# VSCard_v2.net
KiCad netlist of a schematic drawn in EAGLE
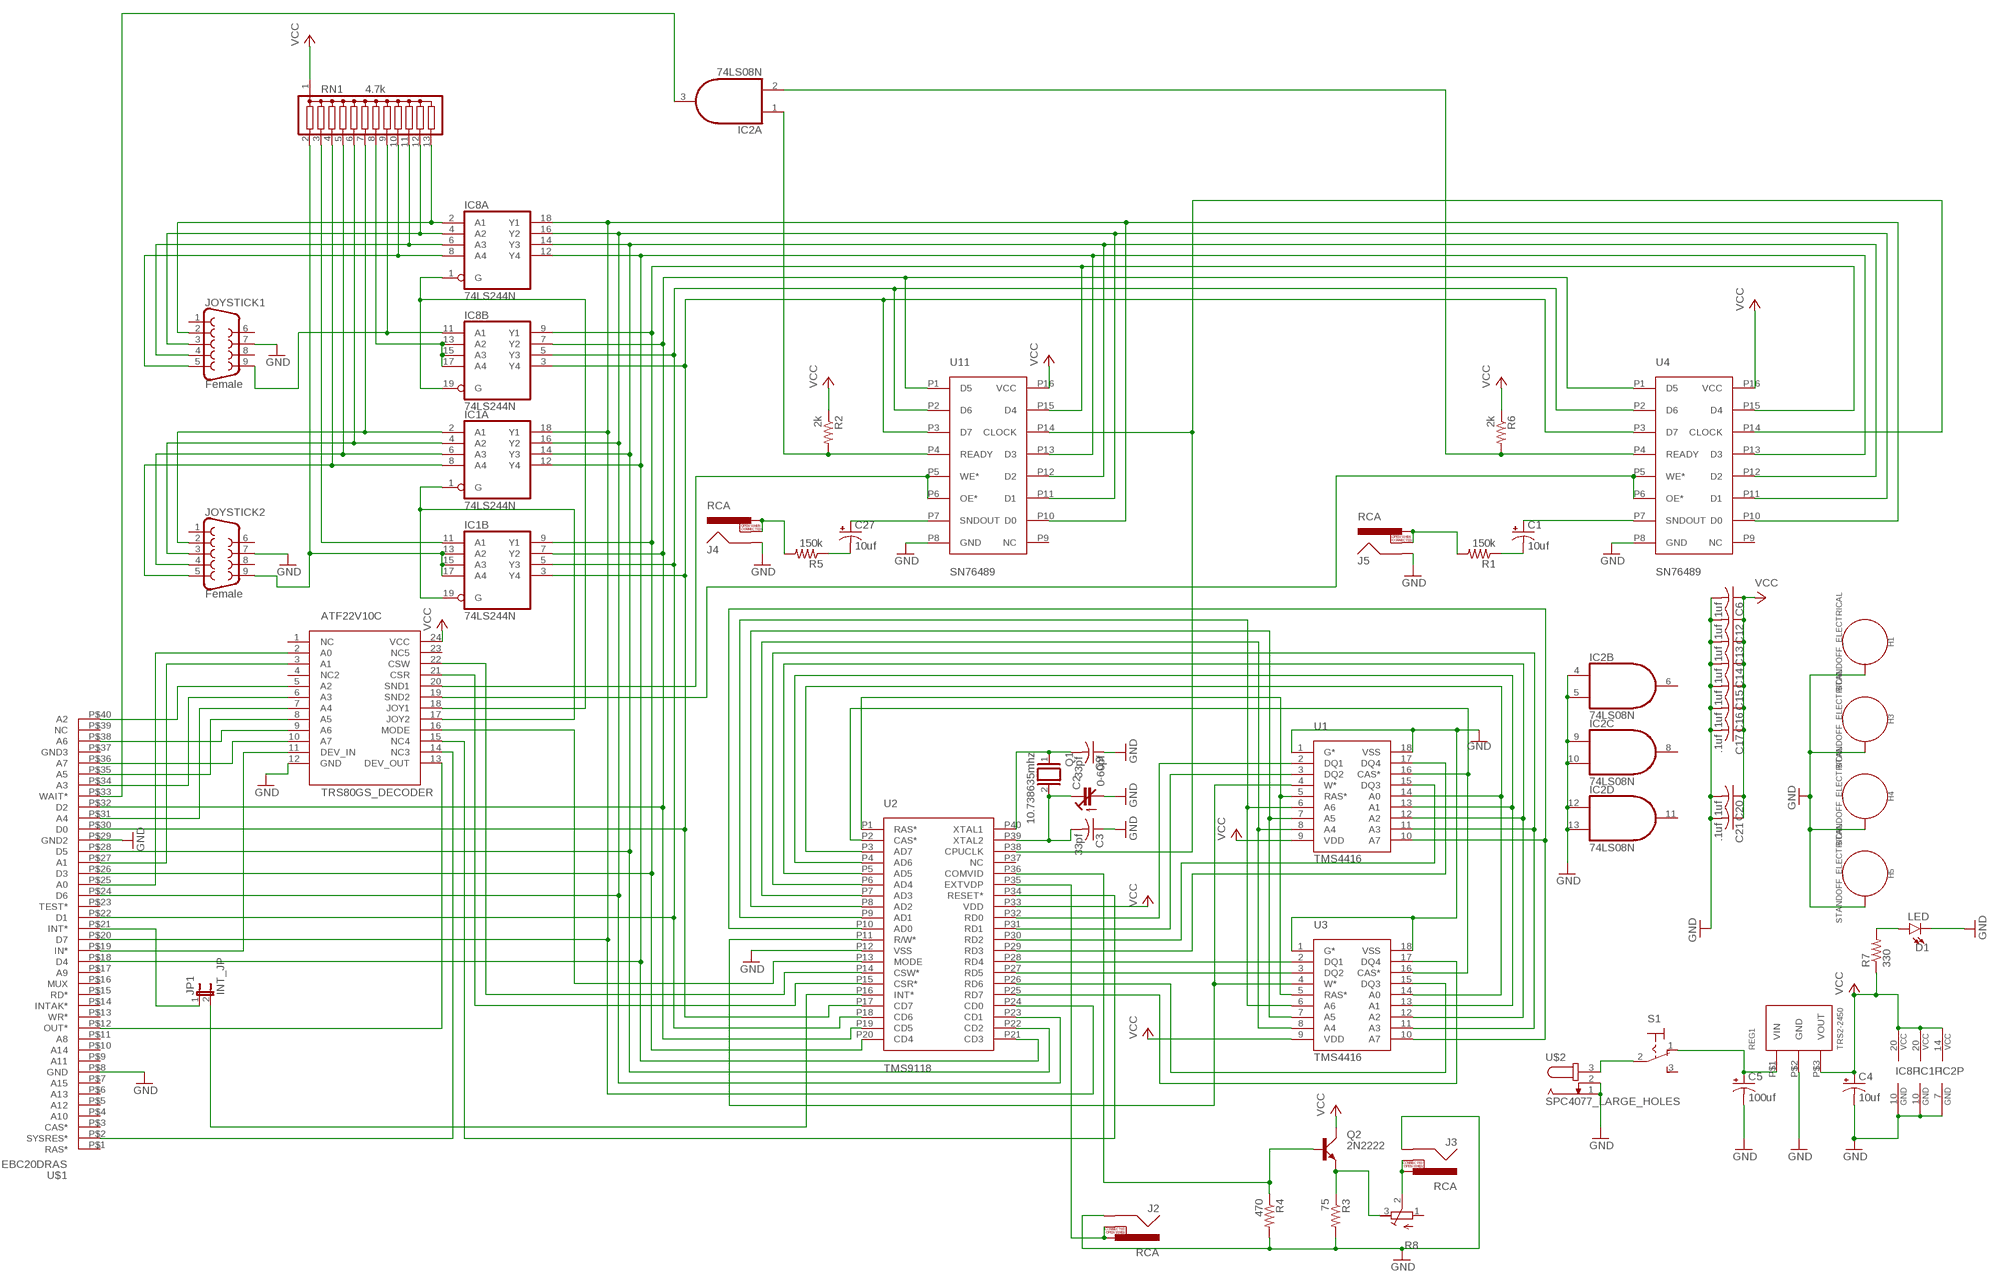
[diagram p0: schematic, sheet 1]

(export (version "E")
  (design (tool "Eeschema 10.0.6"))
  (components
    (comp (ref "ATF22V10C")
      (value "TRS80GS_DECODER")
      (footprint "eagle-import:DIP24SKI")
      (libsource (lib "eagle-import") (part "TRS80GS_DECODER"))
    )
    (comp (ref "C1")
      (value "10uf")
      (footprint "eagle-import:E2,5-6")
      (libsource (lib "eagle-import") (part "resistor_348_CPOL-USE2.5-6"))
    )
    (comp (ref "C2")
      (value "0-60pf")
      (footprint "eagle-import:CTRIM3050.504")
      (libsource (lib "eagle-import") (part "C-TRIMM3050.504"))
    )
    (comp (ref "C3")
      (value "33pf")
      (footprint "eagle-import:C050-050X075")
      (libsource (lib "eagle-import") (part "C-US050-050X075"))
    )
    (comp (ref "C4")
      (value "10uf")
      (footprint "eagle-import:E2,5-5")
      (libsource (lib "eagle-import") (part "resistor_348_CPOL-USE2.5-5"))
    )
    (comp (ref "C5")
      (value "100uf")
      (footprint "eagle-import:E3,5-10")
      (libsource (lib "eagle-import") (part "CPOL-USE3.5-10"))
    )
    (comp (ref "C6")
      (value ".1uf")
      (footprint "eagle-import:C025-025X050")
      (libsource (lib "eagle-import") (part "resistor_348_C-US025-025X050"))
    )
    (comp (ref "C9")
      (value "33pf")
      (footprint "eagle-import:C050-050X075")
      (libsource (lib "eagle-import") (part "C-US050-050X075"))
    )
    (comp (ref "C12")
      (value ".1uf")
      (footprint "eagle-import:C025-025X050")
      (libsource (lib "eagle-import") (part "resistor_348_C-US025-025X050"))
    )
    (comp (ref "C13")
      (value ".1uf")
      (footprint "eagle-import:C025-025X050")
      (libsource (lib "eagle-import") (part "resistor_348_C-US025-025X050"))
    )
    (comp (ref "C14")
      (value ".1uf")
      (footprint "eagle-import:C025-025X050")
      (libsource (lib "eagle-import") (part "resistor_348_C-US025-025X050"))
    )
    (comp (ref "C15")
      (value ".1uf")
      (footprint "eagle-import:C025-025X050")
      (libsource (lib "eagle-import") (part "resistor_348_C-US025-025X050"))
    )
    (comp (ref "C16")
      (value ".1uf")
      (footprint "eagle-import:C025-025X050")
      (libsource (lib "eagle-import") (part "resistor_348_C-US025-025X050"))
    )
    (comp (ref "C17")
      (value ".1uf")
      (footprint "eagle-import:C025-025X050")
      (libsource (lib "eagle-import") (part "resistor_348_C-US025-025X050"))
    )
    (comp (ref "C20")
      (value ".1uf")
      (footprint "eagle-import:C025-025X050")
      (libsource (lib "eagle-import") (part "resistor_348_C-US025-025X050"))
    )
    (comp (ref "C21")
      (value ".1uf")
      (footprint "eagle-import:C025-025X050")
      (libsource (lib "eagle-import") (part "resistor_348_C-US025-025X050"))
    )
    (comp (ref "C27")
      (value "10uf")
      (footprint "eagle-import:E2,5-6")
      (libsource (lib "eagle-import") (part "resistor_348_CPOL-USE2.5-6"))
    )
    (comp (ref "D1")
      (value "LED")
      (footprint "eagle-import:LED_3MM")
      (libsource (lib "eagle-import") (part "LED3MM"))
    )
    (comp (ref "H1")
      (value "STANDOFF_ELECTRICAL")
      (footprint "eagle-import:STANDOFF-ELECTRICAL")
      (libsource (lib "eagle-import") (part "STANDOFF_ELECTRICAL"))
    )
    (comp (ref "H3")
      (value "STANDOFF_ELECTRICAL")
      (footprint "eagle-import:STANDOFF-ELECTRICAL")
      (libsource (lib "eagle-import") (part "STANDOFF_ELECTRICAL"))
    )
    (comp (ref "H4")
      (value "STANDOFF_ELECTRICAL")
      (footprint "eagle-import:STANDOFF-ELECTRICAL")
      (libsource (lib "eagle-import") (part "STANDOFF_ELECTRICAL"))
    )
    (comp (ref "H5")
      (value "STANDOFF_ELECTRICAL")
      (footprint "eagle-import:STANDOFF-ELECTRICAL")
      (libsource (lib "eagle-import") (part "STANDOFF_ELECTRICAL"))
    )
    (comp (ref "IC1")
      (value "74LS244N")
      (footprint "eagle-import:DIL20")
      (libsource (lib "eagle-import") (part "74244NLS"))
    )
    (comp (ref "IC2")
      (value "74LS08N")
      (footprint "eagle-import:DIL14")
      (libsource (lib "eagle-import") (part "7408NLS"))
    )
    (comp (ref "IC8")
      (value "74LS244N")
      (footprint "eagle-import:DIL20")
      (libsource (lib "eagle-import") (part "74244NLS"))
    )
    (comp (ref "J2")
      (value "RCA")
      (footprint "eagle-import:RCA")
      (libsource (lib "eagle-import") (part "RCA"))
    )
    (comp (ref "J3")
      (value "RCA")
      (footprint "eagle-import:RCA")
      (libsource (lib "eagle-import") (part "RCA"))
    )
    (comp (ref "J4")
      (value "RCA")
      (footprint "eagle-import:RCA")
      (libsource (lib "eagle-import") (part "RCA"))
    )
    (comp (ref "J5")
      (value "RCA")
      (footprint "eagle-import:RCA")
      (libsource (lib "eagle-import") (part "RCA"))
    )
    (comp (ref "JOYSTICK1")
      (value "Female")
      (footprint "eagle-import:DB9")
      (libsource (lib "eagle-import") (part "DB9FEMALE"))
    )
    (comp (ref "JOYSTICK2")
      (value "Female")
      (footprint "eagle-import:DB9")
      (libsource (lib "eagle-import") (part "DB9FEMALE"))
    )
    (comp (ref "JP1")
      (value "INT_JP")
      (footprint "eagle-import:JP1")
      (libsource (lib "eagle-import") (part "JP1E"))
    )
    (comp (ref "Q1")
      (value "10.738635mhz")
      (footprint "eagle-import:QS")
      (libsource (lib "eagle-import") (part "XTAL/S"))
    )
    (comp (ref "Q2")
      (value "2N2222")
      (footprint "eagle-import:TO18A")
      (libsource (lib "eagle-import") (part "2N2222"))
    )
    (comp (ref "R1")
      (value "150k")
      (footprint "eagle-import:0207_2V")
      (libsource (lib "eagle-import") (part "R-US_0207/2V"))
    )
    (comp (ref "R2")
      (value "2k")
      (footprint "eagle-import:0207_2V")
      (libsource (lib "eagle-import") (part "R-US_0207/2V"))
    )
    (comp (ref "R3")
      (value "75")
      (footprint "eagle-import:0207_2V")
      (libsource (lib "eagle-import") (part "R-US_0207/2V"))
    )
    (comp (ref "R4")
      (value "470")
      (footprint "eagle-import:0207_2V")
      (libsource (lib "eagle-import") (part "R-US_0207/2V"))
    )
    (comp (ref "R5")
      (value "150k")
      (footprint "eagle-import:0207_2V")
      (libsource (lib "eagle-import") (part "R-US_0207/2V"))
    )
    (comp (ref "R6")
      (value "2k")
      (footprint "eagle-import:0207_2V")
      (libsource (lib "eagle-import") (part "R-US_0207/2V"))
    )
    (comp (ref "R7")
      (value "330")
      (footprint "eagle-import:0309V")
      (libsource (lib "eagle-import") (part "R-US_0309/V"))
    )
    (comp (ref "R8")
      (value "R-TRIMM64W")
      (footprint "eagle-import:RTRIM64W")
      (libsource (lib "eagle-import") (part "R-TRIMM64W"))
    )
    (comp (ref "REG1")
      (value "TRS2-2450")
      (footprint "eagle-import:TRACON_REG")
      (libsource (lib "eagle-import") (part "TRS2-2450"))
    )
    (comp (ref "RN1")
      (value "4.7k")
      (footprint "eagle-import:SIL13")
      (libsource (lib "eagle-import") (part "G12R"))
    )
    (comp (ref "S1")
      (value "320-916")
      (footprint "eagle-import:320-916")
      (libsource (lib "eagle-import") (part "320-916"))
    )
    (comp (ref "U$1")
      (value "EBC20DRAS")
      (footprint "eagle-import:EBC20DRAS")
      (libsource (lib "eagle-import") (part "EBC20DRAS"))
    )
    (comp (ref "U$2")
      (value "SPC4077_LARGE_HOLES")
      (footprint "eagle-import:SPC4077")
      (libsource (lib "eagle-import") (part "SPC4077_LARGE_HOLES"))
    )
    (comp (ref "U1")
      (value "TMS4416")
      (footprint "eagle-import:DIP18")
      (libsource (lib "eagle-import") (part "TMS4416"))
    )
    (comp (ref "U2")
      (value "TMS9118")
      (footprint "eagle-import:DIP40_MCU")
      (libsource (lib "eagle-import") (part "TMS9118"))
    )
    (comp (ref "U3")
      (value "TMS4416")
      (footprint "eagle-import:DIP18")
      (libsource (lib "eagle-import") (part "TMS4416"))
    )
    (comp (ref "U4")
      (value "SN76489")
      (footprint "eagle-import:DIP16")
      (libsource (lib "eagle-import") (part "SN76489"))
    )
    (comp (ref "U11")
      (value "SN76489")
      (footprint "eagle-import:DIP16")
      (libsource (lib "eagle-import") (part "SN76489"))
    )
  )
  (nets
    (net (code "1") (name "GND") (class "Default")
      (node (ref "ATF22V10C") (pin "12") (pinfunction "GND_12") (pintype "bidirectional"))
      (node (ref "C12") (pin "2") (pinfunction "2_2") (pintype "passive"))
      (node (ref "C13") (pin "2") (pinfunction "2_2") (pintype "passive"))
      (node (ref "C14") (pin "2") (pinfunction "2_2") (pintype "passive"))
      (node (ref "C15") (pin "2") (pinfunction "2_2") (pintype "passive"))
      (node (ref "C16") (pin "2") (pinfunction "2_2") (pintype "passive"))
      (node (ref "C17") (pin "2") (pinfunction "2_2") (pintype "passive"))
      (node (ref "C2") (pin "2") (pinfunction "A_2") (pintype "passive"))
      (node (ref "C20") (pin "2") (pinfunction "2_2") (pintype "passive"))
      (node (ref "C21") (pin "2") (pinfunction "2_2") (pintype "passive"))
      (node (ref "C3") (pin "1") (pinfunction "1_1") (pintype "passive"))
      (node (ref "C4") (pin "-") (pinfunction "-_-") (pintype "passive"))
      (node (ref "C5") (pin "-") (pinfunction "-_-") (pintype "passive"))
      (node (ref "C6") (pin "2") (pinfunction "2_2") (pintype "passive"))
      (node (ref "C9") (pin "1") (pinfunction "1_1") (pintype "passive"))
      (node (ref "D1") (pin "K") (pinfunction "C_K") (pintype "passive"))
      (node (ref "H1") (pin "P1") (pinfunction "P$1_P1") (pintype "bidirectional"))
      (node (ref "H3") (pin "P1") (pinfunction "P$1_P1") (pintype "bidirectional"))
      (node (ref "H4") (pin "P1") (pinfunction "P$1_P1") (pintype "bidirectional"))
      (node (ref "H5") (pin "P1") (pinfunction "P$1_P1") (pintype "bidirectional"))
      (node (ref "IC1") (pin "10") (pinfunction "GND_10") (pintype "power_in"))
      (node (ref "IC2") (pin "10") (pinfunction "I1_10") (pintype "input"))
      (node (ref "IC2") (pin "12") (pinfunction "I0_12") (pintype "input"))
      (node (ref "IC2") (pin "13") (pinfunction "I1_13") (pintype "input"))
      (node (ref "IC2") (pin "4") (pinfunction "I0_4") (pintype "input"))
      (node (ref "IC2") (pin "5") (pinfunction "I1_5") (pintype "input"))
      (node (ref "IC2") (pin "7") (pinfunction "GND_7") (pintype "power_in"))
      (node (ref "IC2") (pin "9") (pinfunction "I0_9") (pintype "input"))
      (node (ref "IC8") (pin "10") (pinfunction "GND_10") (pintype "power_in"))
      (node (ref "J2") (pin "SHELL") (pinfunction "SHELL_SHELL") (pintype "bidirectional"))
      (node (ref "J3") (pin "SHELL") (pinfunction "SHELL_SHELL") (pintype "bidirectional"))
      (node (ref "J4") (pin "SHELL") (pinfunction "SHELL_SHELL") (pintype "bidirectional"))
      (node (ref "J5") (pin "SHELL") (pinfunction "SHELL_SHELL") (pintype "bidirectional"))
      (node (ref "JOYSTICK1") (pin "7") (pinfunction "7_7") (pintype "passive"))
      (node (ref "JOYSTICK2") (pin "7") (pinfunction "7_7") (pintype "passive"))
      (node (ref "R3") (pin "2") (pinfunction "2_2") (pintype "passive"))
      (node (ref "R4") (pin "2") (pinfunction "2_2") (pintype "passive"))
      (node (ref "REG1") (pin "P$2") (pinfunction "GND_P$2") (pintype "bidirectional"))
      (node (ref "U$1") (pin "P$29") (pinfunction "GND2_P$29") (pintype "bidirectional"))
      (node (ref "U$1") (pin "P$8") (pinfunction "GND_P$8") (pintype "bidirectional"))
      (node (ref "U$2") (pin "1") (pinfunction "1_1") (pintype "passive"))
      (node (ref "U$2") (pin "2") (pinfunction "2_2") (pintype "passive"))
      (node (ref "U1") (pin "1") (pinfunction "G*_1") (pintype "bidirectional"))
      (node (ref "U1") (pin "18") (pinfunction "VSS_18") (pintype "bidirectional"))
      (node (ref "U11") (pin "P8") (pinfunction "GND_P8") (pintype "bidirectional"))
      (node (ref "U2") (pin "P12") (pinfunction "VSS_P12") (pintype "bidirectional"))
      (node (ref "U3") (pin "1") (pinfunction "G*_1") (pintype "bidirectional"))
      (node (ref "U3") (pin "18") (pinfunction "VSS_18") (pintype "bidirectional"))
      (node (ref "U4") (pin "P8") (pinfunction "GND_P8") (pintype "bidirectional"))
    )
    (net (code "2") (name "Net-(ATF22V10C-A0)") (class "Default")
      (node (ref "ATF22V10C") (pin "2") (pinfunction "A0_2") (pintype "bidirectional"))
      (node (ref "U$1") (pin "P$25") (pinfunction "A0_P$25") (pintype "bidirectional"))
    )
    (net (code "3") (name "Net-(ATF22V10C-A1)") (class "Default")
      (node (ref "ATF22V10C") (pin "3") (pinfunction "A1_3") (pintype "bidirectional"))
      (node (ref "U$1") (pin "P$27") (pinfunction "A1_P$27") (pintype "bidirectional"))
    )
    (net (code "4") (name "Net-(ATF22V10C-A2)") (class "Default")
      (node (ref "ATF22V10C") (pin "5") (pinfunction "A2_5") (pintype "bidirectional"))
      (node (ref "U$1") (pin "P$40") (pinfunction "A2_P$40") (pintype "bidirectional"))
    )
    (net (code "5") (name "Net-(ATF22V10C-A3)") (class "Default")
      (node (ref "ATF22V10C") (pin "6") (pinfunction "A3_6") (pintype "bidirectional"))
      (node (ref "U$1") (pin "P$34") (pinfunction "A3_P$34") (pintype "bidirectional"))
    )
    (net (code "6") (name "Net-(ATF22V10C-A4)") (class "Default")
      (node (ref "ATF22V10C") (pin "7") (pinfunction "A4_7") (pintype "bidirectional"))
      (node (ref "U$1") (pin "P$31") (pinfunction "A4_P$31") (pintype "bidirectional"))
    )
    (net (code "7") (name "Net-(ATF22V10C-A5)") (class "Default")
      (node (ref "ATF22V10C") (pin "8") (pinfunction "A5_8") (pintype "bidirectional"))
      (node (ref "U$1") (pin "P$35") (pinfunction "A5_P$35") (pintype "bidirectional"))
    )
    (net (code "8") (name "Net-(ATF22V10C-A6)") (class "Default")
      (node (ref "ATF22V10C") (pin "9") (pinfunction "A6_9") (pintype "bidirectional"))
      (node (ref "U$1") (pin "P$38") (pinfunction "A6_P$38") (pintype "bidirectional"))
    )
    (net (code "9") (name "Net-(ATF22V10C-A7)") (class "Default")
      (node (ref "ATF22V10C") (pin "10") (pinfunction "A7_10") (pintype "bidirectional"))
      (node (ref "U$1") (pin "P$36") (pinfunction "A7_P$36") (pintype "bidirectional"))
    )
    (net (code "10") (name "Net-(ATF22V10C-CSR)") (class "Default")
      (node (ref "ATF22V10C") (pin "21") (pinfunction "CSR_21") (pintype "bidirectional"))
      (node (ref "U2") (pin "P15") (pinfunction "CSR*_P15") (pintype "bidirectional"))
    )
    (net (code "11") (name "Net-(ATF22V10C-CSW)") (class "Default")
      (node (ref "ATF22V10C") (pin "22") (pinfunction "CSW_22") (pintype "bidirectional"))
      (node (ref "U2") (pin "P14") (pinfunction "CSW*_P14") (pintype "bidirectional"))
    )
    (net (code "12") (name "Net-(ATF22V10C-DEV_IN)") (class "Default")
      (node (ref "ATF22V10C") (pin "11") (pinfunction "DEV_IN_11") (pintype "bidirectional"))
      (node (ref "U$1") (pin "P$19") (pinfunction "IN*_P$19") (pintype "bidirectional"))
    )
    (net (code "13") (name "Net-(ATF22V10C-DEV_OUT)") (class "Default")
      (node (ref "ATF22V10C") (pin "13") (pinfunction "DEV_OUT_13") (pintype "bidirectional"))
      (node (ref "U$1") (pin "P$12") (pinfunction "OUT*_P$12") (pintype "bidirectional"))
    )
    (net (code "14") (name "Net-(ATF22V10C-JOY1)") (class "Default")
      (node (ref "ATF22V10C") (pin "18") (pinfunction "JOY1_18") (pintype "bidirectional"))
      (node (ref "IC8") (pin "1") (pinfunction "G_1") (pintype "input"))
      (node (ref "IC8") (pin "19") (pinfunction "G_19") (pintype "input"))
    )
    (net (code "15") (name "Net-(ATF22V10C-JOY2)") (class "Default")
      (node (ref "ATF22V10C") (pin "17") (pinfunction "JOY2_17") (pintype "bidirectional"))
      (node (ref "IC1") (pin "1") (pinfunction "G_1") (pintype "input"))
      (node (ref "IC1") (pin "19") (pinfunction "G_19") (pintype "input"))
    )
    (net (code "16") (name "Net-(ATF22V10C-MODE)") (class "Default")
      (node (ref "ATF22V10C") (pin "16") (pinfunction "MODE_16") (pintype "bidirectional"))
      (node (ref "U2") (pin "P13") (pinfunction "MODE_P13") (pintype "bidirectional"))
    )
    (net (code "17") (name "Net-(ATF22V10C-NC3)") (class "Default")
      (node (ref "ATF22V10C") (pin "14") (pinfunction "NC3_14") (pintype "bidirectional"))
      (node (ref "U$1") (pin "P$2") (pinfunction "SYSRES*_P$2") (pintype "bidirectional"))
    )
    (net (code "18") (name "Net-(ATF22V10C-NC4)") (class "Default")
      (node (ref "ATF22V10C") (pin "15") (pinfunction "NC4_15") (pintype "bidirectional"))
      (node (ref "U2") (pin "P34") (pinfunction "RESET*_P34") (pintype "bidirectional"))
    )
    (net (code "19") (name "Net-(ATF22V10C-SND1)") (class "Default")
      (node (ref "ATF22V10C") (pin "20") (pinfunction "SND1_20") (pintype "bidirectional"))
      (node (ref "U11") (pin "P5") (pinfunction "WE*_P5") (pintype "bidirectional"))
      (node (ref "U11") (pin "P6") (pinfunction "OE*_P6") (pintype "bidirectional"))
    )
    (net (code "20") (name "Net-(ATF22V10C-SND2)") (class "Default")
      (node (ref "ATF22V10C") (pin "19") (pinfunction "SND2_19") (pintype "bidirectional"))
      (node (ref "U4") (pin "P5") (pinfunction "WE*_P5") (pintype "bidirectional"))
      (node (ref "U4") (pin "P6") (pinfunction "OE*_P6") (pintype "bidirectional"))
    )
    (net (code "21") (name "Net-(C1-Pad-)") (class "Default")
      (node (ref "C1") (pin "-") (pinfunction "-_-") (pintype "passive"))
      (node (ref "R1") (pin "1") (pinfunction "1_1") (pintype "passive"))
    )
    (net (code "22") (name "Net-(C2-E)") (class "Default")
      (node (ref "C2") (pin "1") (pinfunction "E_1") (pintype "passive"))
      (node (ref "C3") (pin "2") (pinfunction "2_2") (pintype "passive"))
      (node (ref "Q1") (pin "2") (pinfunction "2_2") (pintype "passive"))
      (node (ref "U2") (pin "P39") (pinfunction "XTAL2_P39") (pintype "bidirectional"))
    )
    (net (code "23") (name "Net-(C27-Pad-)") (class "Default")
      (node (ref "C27") (pin "-") (pinfunction "-_-") (pintype "passive"))
      (node (ref "R5") (pin "1") (pinfunction "1_1") (pintype "passive"))
    )
    (net (code "24") (name "Net-(D1-PadA)") (class "Default")
      (node (ref "D1") (pin "A") (pinfunction "A_A") (pintype "passive"))
      (node (ref "R7") (pin "2") (pinfunction "2_2") (pintype "passive"))
    )
    (net (code "25") (name "Net-(IC1A-A1)") (class "Default")
      (node (ref "IC1") (pin "2") (pinfunction "A1_2") (pintype "input"))
      (node (ref "JOYSTICK2") (pin "2") (pinfunction "2_2") (pintype "passive"))
      (node (ref "RN1") (pin "7") (pinfunction "7_7") (pintype "passive"))
    )
    (net (code "26") (name "Net-(IC1A-A2)") (class "Default")
      (node (ref "IC1") (pin "4") (pinfunction "A2_4") (pintype "input"))
      (node (ref "JOYSTICK2") (pin "3") (pinfunction "3_3") (pintype "passive"))
      (node (ref "RN1") (pin "6") (pinfunction "6_6") (pintype "passive"))
    )
    (net (code "27") (name "Net-(IC1A-A3)") (class "Default")
      (node (ref "IC1") (pin "6") (pinfunction "A3_6") (pintype "input"))
      (node (ref "JOYSTICK2") (pin "4") (pinfunction "4_4") (pintype "passive"))
      (node (ref "RN1") (pin "5") (pinfunction "5_5") (pintype "passive"))
    )
    (net (code "28") (name "Net-(IC1A-A4)") (class "Default")
      (node (ref "IC1") (pin "8") (pinfunction "A4_8") (pintype "input"))
      (node (ref "JOYSTICK2") (pin "5") (pinfunction "5_5") (pintype "passive"))
      (node (ref "RN1") (pin "4") (pinfunction "4_4") (pintype "passive"))
    )
    (net (code "29") (name "Net-(IC1A-Y1)") (class "Default")
      (node (ref "IC1") (pin "18") (pinfunction "Y1_18") (pintype "tri_state"))
      (node (ref "IC8") (pin "18") (pinfunction "Y1_18") (pintype "tri_state"))
      (node (ref "U$1") (pin "P$20") (pinfunction "D7_P$20") (pintype "bidirectional"))
      (node (ref "U11") (pin "P10") (pinfunction "D0_P10") (pintype "bidirectional"))
      (node (ref "U2") (pin "P24") (pinfunction "CD0_P24") (pintype "bidirectional"))
      (node (ref "U4") (pin "P10") (pinfunction "D0_P10") (pintype "bidirectional"))
    )
    (net (code "30") (name "Net-(IC1A-Y2)") (class "Default")
      (node (ref "IC1") (pin "16") (pinfunction "Y2_16") (pintype "tri_state"))
      (node (ref "IC8") (pin "16") (pinfunction "Y2_16") (pintype "tri_state"))
      (node (ref "U$1") (pin "P$24") (pinfunction "D6_P$24") (pintype "bidirectional"))
      (node (ref "U11") (pin "P11") (pinfunction "D1_P11") (pintype "bidirectional"))
      (node (ref "U2") (pin "P23") (pinfunction "CD1_P23") (pintype "bidirectional"))
      (node (ref "U4") (pin "P11") (pinfunction "D1_P11") (pintype "bidirectional"))
    )
    (net (code "31") (name "Net-(IC1A-Y3)") (class "Default")
      (node (ref "IC1") (pin "14") (pinfunction "Y3_14") (pintype "tri_state"))
      (node (ref "IC8") (pin "14") (pinfunction "Y3_14") (pintype "tri_state"))
      (node (ref "U$1") (pin "P$28") (pinfunction "D5_P$28") (pintype "bidirectional"))
      (node (ref "U11") (pin "P12") (pinfunction "D2_P12") (pintype "bidirectional"))
      (node (ref "U2") (pin "P22") (pinfunction "CD2_P22") (pintype "bidirectional"))
      (node (ref "U4") (pin "P12") (pinfunction "D2_P12") (pintype "bidirectional"))
    )
    (net (code "32") (name "Net-(IC1A-Y4)") (class "Default")
      (node (ref "IC1") (pin "12") (pinfunction "Y4_12") (pintype "tri_state"))
      (node (ref "IC8") (pin "12") (pinfunction "Y4_12") (pintype "tri_state"))
      (node (ref "U$1") (pin "P$18") (pinfunction "D4_P$18") (pintype "bidirectional"))
      (node (ref "U11") (pin "P13") (pinfunction "D3_P13") (pintype "bidirectional"))
      (node (ref "U2") (pin "P21") (pinfunction "CD3_P21") (pintype "bidirectional"))
      (node (ref "U4") (pin "P13") (pinfunction "D3_P13") (pintype "bidirectional"))
    )
    (net (code "33") (name "Net-(IC1B-A1)") (class "Default")
      (node (ref "IC1") (pin "11") (pinfunction "A1_11") (pintype "input"))
      (node (ref "RN1") (pin "3") (pinfunction "3_3") (pintype "passive"))
    )
    (net (code "34") (name "Net-(IC1B-A2)") (class "Default")
      (node (ref "IC1") (pin "13") (pinfunction "A2_13") (pintype "input"))
      (node (ref "IC1") (pin "15") (pinfunction "A3_15") (pintype "input"))
      (node (ref "IC1") (pin "17") (pinfunction "A4_17") (pintype "input"))
      (node (ref "JOYSTICK2") (pin "9") (pinfunction "9_9") (pintype "passive"))
      (node (ref "RN1") (pin "2") (pinfunction "2_2") (pintype "passive"))
    )
    (net (code "35") (name "Net-(IC1B-Y1)") (class "Default")
      (node (ref "IC1") (pin "9") (pinfunction "Y1_9") (pintype "tri_state"))
      (node (ref "IC8") (pin "9") (pinfunction "Y1_9") (pintype "tri_state"))
      (node (ref "U$1") (pin "P$26") (pinfunction "D3_P$26") (pintype "bidirectional"))
      (node (ref "U11") (pin "P15") (pinfunction "D4_P15") (pintype "bidirectional"))
      (node (ref "U2") (pin "P20") (pinfunction "CD4_P20") (pintype "bidirectional"))
      (node (ref "U4") (pin "P15") (pinfunction "D4_P15") (pintype "bidirectional"))
    )
    (net (code "36") (name "Net-(IC1B-Y2)") (class "Default")
      (node (ref "IC1") (pin "7") (pinfunction "Y2_7") (pintype "tri_state"))
      (node (ref "IC8") (pin "7") (pinfunction "Y2_7") (pintype "tri_state"))
      (node (ref "U$1") (pin "P$32") (pinfunction "D2_P$32") (pintype "bidirectional"))
      (node (ref "U11") (pin "P1") (pinfunction "D5_P1") (pintype "bidirectional"))
      (node (ref "U2") (pin "P19") (pinfunction "CD5_P19") (pintype "bidirectional"))
      (node (ref "U4") (pin "P1") (pinfunction "D5_P1") (pintype "bidirectional"))
    )
    (net (code "37") (name "Net-(IC1B-Y3)") (class "Default")
      (node (ref "IC1") (pin "5") (pinfunction "Y3_5") (pintype "tri_state"))
      (node (ref "IC8") (pin "5") (pinfunction "Y3_5") (pintype "tri_state"))
      (node (ref "U$1") (pin "P$22") (pinfunction "D1_P$22") (pintype "bidirectional"))
      (node (ref "U11") (pin "P2") (pinfunction "D6_P2") (pintype "bidirectional"))
      (node (ref "U2") (pin "P18") (pinfunction "CD6_P18") (pintype "bidirectional"))
      (node (ref "U4") (pin "P2") (pinfunction "D6_P2") (pintype "bidirectional"))
    )
    (net (code "38") (name "Net-(IC1B-Y4)") (class "Default")
      (node (ref "IC1") (pin "3") (pinfunction "Y4_3") (pintype "tri_state"))
      (node (ref "IC8") (pin "3") (pinfunction "Y4_3") (pintype "tri_state"))
      (node (ref "U$1") (pin "P$30") (pinfunction "D0_P$30") (pintype "bidirectional"))
      (node (ref "U11") (pin "P3") (pinfunction "D7_P3") (pintype "bidirectional"))
      (node (ref "U2") (pin "P17") (pinfunction "CD7_P17") (pintype "bidirectional"))
      (node (ref "U4") (pin "P3") (pinfunction "D7_P3") (pintype "bidirectional"))
    )
    (net (code "39") (name "Net-(IC2A-I0)") (class "Default")
      (node (ref "IC2") (pin "1") (pinfunction "I0_1") (pintype "input"))
      (node (ref "R2") (pin "2") (pinfunction "2_2") (pintype "passive"))
      (node (ref "U11") (pin "P4") (pinfunction "READY_P4") (pintype "bidirectional"))
    )
    (net (code "40") (name "Net-(IC2A-I1)") (class "Default")
      (node (ref "IC2") (pin "2") (pinfunction "I1_2") (pintype "input"))
      (node (ref "R6") (pin "2") (pinfunction "2_2") (pintype "passive"))
      (node (ref "U4") (pin "P4") (pinfunction "READY_P4") (pintype "bidirectional"))
    )
    (net (code "41") (name "Net-(IC2A-O)") (class "Default")
      (node (ref "IC2") (pin "3") (pinfunction "O_3") (pintype "output"))
      (node (ref "U$1") (pin "P$33") (pinfunction "WAIT*_P$33") (pintype "bidirectional"))
    )
    (net (code "42") (name "Net-(IC8A-A1)") (class "Default")
      (node (ref "IC8") (pin "2") (pinfunction "A1_2") (pintype "input"))
      (node (ref "JOYSTICK1") (pin "2") (pinfunction "2_2") (pintype "passive"))
      (node (ref "RN1") (pin "13") (pinfunction "13_13") (pintype "passive"))
    )
    (net (code "43") (name "Net-(IC8A-A2)") (class "Default")
      (node (ref "IC8") (pin "4") (pinfunction "A2_4") (pintype "input"))
      (node (ref "JOYSTICK1") (pin "3") (pinfunction "3_3") (pintype "passive"))
      (node (ref "RN1") (pin "12") (pinfunction "12_12") (pintype "passive"))
    )
    (net (code "44") (name "Net-(IC8A-A3)") (class "Default")
      (node (ref "IC8") (pin "6") (pinfunction "A3_6") (pintype "input"))
      (node (ref "JOYSTICK1") (pin "4") (pinfunction "4_4") (pintype "passive"))
      (node (ref "RN1") (pin "11") (pinfunction "11_11") (pintype "passive"))
    )
    (net (code "45") (name "Net-(IC8A-A4)") (class "Default")
      (node (ref "IC8") (pin "8") (pinfunction "A4_8") (pintype "input"))
      (node (ref "JOYSTICK1") (pin "5") (pinfunction "5_5") (pintype "passive"))
      (node (ref "RN1") (pin "10") (pinfunction "10_10") (pintype "passive"))
    )
    (net (code "46") (name "Net-(IC8B-A1)") (class "Default")
      (node (ref "IC8") (pin "11") (pinfunction "A1_11") (pintype "input"))
      (node (ref "JOYSTICK1") (pin "9") (pinfunction "9_9") (pintype "passive"))
      (node (ref "RN1") (pin "9") (pinfunction "9_9") (pintype "passive"))
    )
    (net (code "47") (name "Net-(IC8B-A2)") (class "Default")
      (node (ref "IC8") (pin "13") (pinfunction "A2_13") (pintype "input"))
      (node (ref "IC8") (pin "15") (pinfunction "A3_15") (pintype "input"))
      (node (ref "IC8") (pin "17") (pinfunction "A4_17") (pintype "input"))
      (node (ref "RN1") (pin "8") (pinfunction "8_8") (pintype "passive"))
    )
    (net (code "48") (name "Net-(J4-PadPIN)") (class "Default")
      (node (ref "J4") (pin "PIN") (pinfunction "PIN_PIN") (pintype "bidirectional"))
      (node (ref "J4") (pin "SWITCH") (pinfunction "SWITCH_SWITCH") (pintype "bidirectional"))
      (node (ref "R5") (pin "2") (pinfunction "2_2") (pintype "passive"))
    )
    (net (code "49") (name "Net-(J5-PadPIN)") (class "Default")
      (node (ref "J5") (pin "PIN") (pinfunction "PIN_PIN") (pintype "bidirectional"))
      (node (ref "J5") (pin "SWITCH") (pinfunction "SWITCH_SWITCH") (pintype "bidirectional"))
      (node (ref "R1") (pin "2") (pinfunction "2_2") (pintype "passive"))
    )
    (net (code "50") (name "Net-(R8-E)") (class "Default")
      (node (ref "Q2") (pin "E") (pinfunction "E_E") (pintype "passive"))
      (node (ref "R3") (pin "1") (pinfunction "1_1") (pintype "passive"))
      (node (ref "R8") (pin "3") (pinfunction "E_3") (pintype "passive"))
    )
    (net (code "51") (name "Net-(R8-S)") (class "Default")
      (node (ref "J3") (pin "PIN") (pinfunction "PIN_PIN") (pintype "bidirectional"))
      (node (ref "J3") (pin "SWITCH") (pinfunction "SWITCH_SWITCH") (pintype "bidirectional"))
      (node (ref "R8") (pin "2") (pinfunction "S_2") (pintype "passive"))
    )
    (net (code "52") (name "Net-(REG1-VIN)") (class "Default")
      (node (ref "C5") (pin "+") (pinfunction "+_+") (pintype "passive"))
      (node (ref "REG1") (pin "P$1") (pinfunction "VIN_P$1") (pintype "bidirectional"))
      (node (ref "S1") (pin "1") (pinfunction "O_1") (pintype "passive"))
    )
    (net (code "53") (name "Net-(S1-P)") (class "Default")
      (node (ref "S1") (pin "2") (pinfunction "P_2") (pintype "passive"))
      (node (ref "U$2") (pin "3") (pinfunction "3_3") (pintype "passive"))
    )
    (net (code "54") (name "Net-(U$1-INT*)") (class "Default")
      (node (ref "JP1") (pin "1") (pinfunction "1_1") (pintype "passive"))
      (node (ref "U$1") (pin "P$21") (pinfunction "INT*_P$21") (pintype "bidirectional"))
    )
    (net (code "55") (name "Net-(U1-A0)") (class "Default")
      (node (ref "U1") (pin "14") (pinfunction "A0_14") (pintype "bidirectional"))
      (node (ref "U2") (pin "P3") (pinfunction "AD7_P3") (pintype "bidirectional"))
      (node (ref "U3") (pin "14") (pinfunction "A0_14") (pintype "bidirectional"))
    )
    (net (code "56") (name "Net-(U1-A1)") (class "Default")
      (node (ref "U1") (pin "13") (pinfunction "A1_13") (pintype "bidirectional"))
      (node (ref "U2") (pin "P4") (pinfunction "AD6_P4") (pintype "bidirectional"))
      (node (ref "U3") (pin "13") (pinfunction "A1_13") (pintype "bidirectional"))
    )
    (net (code "57") (name "Net-(U1-A2)") (class "Default")
      (node (ref "U1") (pin "12") (pinfunction "A2_12") (pintype "bidirectional"))
      (node (ref "U2") (pin "P5") (pinfunction "AD5_P5") (pintype "bidirectional"))
      (node (ref "U3") (pin "12") (pinfunction "A2_12") (pintype "bidirectional"))
    )
    (net (code "58") (name "Net-(U1-A3)") (class "Default")
      (node (ref "U1") (pin "11") (pinfunction "A3_11") (pintype "bidirectional"))
      (node (ref "U2") (pin "P6") (pinfunction "AD4_P6") (pintype "bidirectional"))
      (node (ref "U3") (pin "11") (pinfunction "A3_11") (pintype "bidirectional"))
    )
    (net (code "59") (name "Net-(U1-A4)") (class "Default")
      (node (ref "U1") (pin "8") (pinfunction "A4_8") (pintype "bidirectional"))
      (node (ref "U2") (pin "P7") (pinfunction "AD3_P7") (pintype "bidirectional"))
      (node (ref "U3") (pin "8") (pinfunction "A4_8") (pintype "bidirectional"))
    )
    (net (code "60") (name "Net-(U1-A5)") (class "Default")
      (node (ref "U1") (pin "7") (pinfunction "A5_7") (pintype "bidirectional"))
      (node (ref "U2") (pin "P8") (pinfunction "AD2_P8") (pintype "bidirectional"))
      (node (ref "U3") (pin "7") (pinfunction "A5_7") (pintype "bidirectional"))
    )
    (net (code "61") (name "Net-(U1-A6)") (class "Default")
      (node (ref "U1") (pin "6") (pinfunction "A6_6") (pintype "bidirectional"))
      (node (ref "U2") (pin "P9") (pinfunction "AD1_P9") (pintype "bidirectional"))
      (node (ref "U3") (pin "6") (pinfunction "A6_6") (pintype "bidirectional"))
    )
    (net (code "62") (name "Net-(U1-A7)") (class "Default")
      (node (ref "U1") (pin "10") (pinfunction "A7_10") (pintype "bidirectional"))
      (node (ref "U2") (pin "P10") (pinfunction "AD0_P10") (pintype "bidirectional"))
      (node (ref "U3") (pin "10") (pinfunction "A7_10") (pintype "bidirectional"))
    )
    (net (code "63") (name "Net-(U1-CAS*)") (class "Default")
      (node (ref "U1") (pin "16") (pinfunction "CAS*_16") (pintype "bidirectional"))
      (node (ref "U2") (pin "P2") (pinfunction "CAS*_P2") (pintype "bidirectional"))
      (node (ref "U3") (pin "16") (pinfunction "CAS*_16") (pintype "bidirectional"))
    )
    (net (code "64") (name "Net-(U1-DQ1)") (class "Default")
      (node (ref "U1") (pin "2") (pinfunction "DQ1_2") (pintype "bidirectional"))
      (node (ref "U2") (pin "P32") (pinfunction "RD0_P32") (pintype "bidirectional"))
    )
    (net (code "65") (name "Net-(U1-DQ2)") (class "Default")
      (node (ref "U1") (pin "3") (pinfunction "DQ2_3") (pintype "bidirectional"))
      (node (ref "U2") (pin "P31") (pinfunction "RD1_P31") (pintype "bidirectional"))
    )
    (net (code "66") (name "Net-(U1-DQ3)") (class "Default")
      (node (ref "U1") (pin "15") (pinfunction "DQ3_15") (pintype "bidirectional"))
      (node (ref "U2") (pin "P30") (pinfunction "RD2_P30") (pintype "bidirectional"))
    )
    (net (code "67") (name "Net-(U1-DQ4)") (class "Default")
      (node (ref "U1") (pin "17") (pinfunction "DQ4_17") (pintype "bidirectional"))
      (node (ref "U2") (pin "P29") (pinfunction "RD3_P29") (pintype "bidirectional"))
    )
    (net (code "68") (name "Net-(U1-RAS*)") (class "Default")
      (node (ref "U1") (pin "5") (pinfunction "RAS*_5") (pintype "bidirectional"))
      (node (ref "U2") (pin "P1") (pinfunction "RAS*_P1") (pintype "bidirectional"))
      (node (ref "U3") (pin "5") (pinfunction "RAS*_5") (pintype "bidirectional"))
    )
    (net (code "69") (name "Net-(U1-W*)") (class "Default")
      (node (ref "U1") (pin "4") (pinfunction "W*_4") (pintype "bidirectional"))
      (node (ref "U2") (pin "P11") (pinfunction "R/W*_P11") (pintype "bidirectional"))
      (node (ref "U3") (pin "4") (pinfunction "W*_4") (pintype "bidirectional"))
    )
    (net (code "70") (name "Net-(U2-COMVID)") (class "Default")
      (node (ref "Q2") (pin "B") (pinfunction "B_B") (pintype "passive"))
      (node (ref "R4") (pin "1") (pinfunction "1_1") (pintype "passive"))
      (node (ref "U2") (pin "P36") (pinfunction "COMVID_P36") (pintype "bidirectional"))
    )
    (net (code "71") (name "Net-(U2-EXTVDP)") (class "Default")
      (node (ref "J2") (pin "PIN") (pinfunction "PIN_PIN") (pintype "bidirectional"))
      (node (ref "J2") (pin "SWITCH") (pinfunction "SWITCH_SWITCH") (pintype "bidirectional"))
      (node (ref "U2") (pin "P35") (pinfunction "EXTVDP_P35") (pintype "bidirectional"))
    )
    (net (code "72") (name "Net-(U2-INT*)") (class "Default")
      (node (ref "JP1") (pin "2") (pinfunction "2_2") (pintype "passive"))
      (node (ref "U2") (pin "P16") (pinfunction "INT*_P16") (pintype "bidirectional"))
    )
    (net (code "73") (name "Net-(U2-RD4)") (class "Default")
      (node (ref "U2") (pin "P28") (pinfunction "RD4_P28") (pintype "bidirectional"))
      (node (ref "U3") (pin "2") (pinfunction "DQ1_2") (pintype "bidirectional"))
    )
    (net (code "74") (name "Net-(U2-RD5)") (class "Default")
      (node (ref "U2") (pin "P27") (pinfunction "RD5_P27") (pintype "bidirectional"))
      (node (ref "U3") (pin "3") (pinfunction "DQ2_3") (pintype "bidirectional"))
    )
    (net (code "75") (name "Net-(U2-RD6)") (class "Default")
      (node (ref "U2") (pin "P26") (pinfunction "RD6_P26") (pintype "bidirectional"))
      (node (ref "U3") (pin "15") (pinfunction "DQ3_15") (pintype "bidirectional"))
    )
    (net (code "76") (name "Net-(U2-RD7)") (class "Default")
      (node (ref "U2") (pin "P25") (pinfunction "RD7_P25") (pintype "bidirectional"))
      (node (ref "U3") (pin "17") (pinfunction "DQ4_17") (pintype "bidirectional"))
    )
    (net (code "77") (name "Net-(U2-XTAL1)") (class "Default")
      (node (ref "C9") (pin "2") (pinfunction "2_2") (pintype "passive"))
      (node (ref "Q1") (pin "1") (pinfunction "1_1") (pintype "passive"))
      (node (ref "U2") (pin "P40") (pinfunction "XTAL1_P40") (pintype "bidirectional"))
    )
    (net (code "78") (name "Net-(U4-SNDOUT)") (class "Default")
      (node (ref "C1") (pin "+") (pinfunction "+_+") (pintype "passive"))
      (node (ref "U4") (pin "P7") (pinfunction "SNDOUT_P7") (pintype "bidirectional"))
    )
    (net (code "79") (name "Net-(U11-CLOCK)") (class "Default")
      (node (ref "U11") (pin "P14") (pinfunction "CLOCK_P14") (pintype "bidirectional"))
      (node (ref "U2") (pin "P38") (pinfunction "CPUCLK_P38") (pintype "bidirectional"))
      (node (ref "U4") (pin "P14") (pinfunction "CLOCK_P14") (pintype "bidirectional"))
    )
    (net (code "80") (name "Net-(U11-SNDOUT)") (class "Default")
      (node (ref "C27") (pin "+") (pinfunction "+_+") (pintype "passive"))
      (node (ref "U11") (pin "P7") (pinfunction "SNDOUT_P7") (pintype "bidirectional"))
    )
    (net (code "81") (name "VCC") (class "Default")
      (node (ref "ATF22V10C") (pin "24") (pinfunction "VCC_24") (pintype "bidirectional"))
      (node (ref "C12") (pin "1") (pinfunction "1_1") (pintype "passive"))
      (node (ref "C13") (pin "1") (pinfunction "1_1") (pintype "passive"))
      (node (ref "C14") (pin "1") (pinfunction "1_1") (pintype "passive"))
      (node (ref "C15") (pin "1") (pinfunction "1_1") (pintype "passive"))
      (node (ref "C16") (pin "1") (pinfunction "1_1") (pintype "passive"))
      (node (ref "C17") (pin "1") (pinfunction "1_1") (pintype "passive"))
      (node (ref "C20") (pin "1") (pinfunction "1_1") (pintype "passive"))
      (node (ref "C21") (pin "1") (pinfunction "1_1") (pintype "passive"))
      (node (ref "C4") (pin "+") (pinfunction "+_+") (pintype "passive"))
      (node (ref "C6") (pin "1") (pinfunction "1_1") (pintype "passive"))
      (node (ref "IC1") (pin "20") (pinfunction "VCC_20") (pintype "power_in"))
      (node (ref "IC2") (pin "14") (pinfunction "VCC_14") (pintype "power_in"))
      (node (ref "IC8") (pin "20") (pinfunction "VCC_20") (pintype "power_in"))
      (node (ref "Q2") (pin "C") (pinfunction "C_C") (pintype "passive"))
      (node (ref "R2") (pin "1") (pinfunction "1_1") (pintype "passive"))
      (node (ref "R6") (pin "1") (pinfunction "1_1") (pintype "passive"))
      (node (ref "R7") (pin "1") (pinfunction "1_1") (pintype "passive"))
      (node (ref "REG1") (pin "P$3") (pinfunction "VOUT_P$3") (pintype "bidirectional"))
      (node (ref "RN1") (pin "1") (pinfunction "1_1") (pintype "passive"))
      (node (ref "U1") (pin "9") (pinfunction "VDD_9") (pintype "bidirectional"))
      (node (ref "U11") (pin "P16") (pinfunction "VCC_P16") (pintype "bidirectional"))
      (node (ref "U2") (pin "P33") (pinfunction "VDD_P33") (pintype "bidirectional"))
      (node (ref "U3") (pin "9") (pinfunction "VDD_9") (pintype "bidirectional"))
      (node (ref "U4") (pin "P16") (pinfunction "VCC_P16") (pintype "bidirectional"))
    )
    (net (code "82") (name "unconnected-(ATF22V10C-NC-Pad1)") (class "Default")
      (node (ref "ATF22V10C") (pin "1") (pinfunction "NC_1") (pintype "bidirectional"))
    )
    (net (code "83") (name "unconnected-(ATF22V10C-NC2-Pad4)") (class "Default")
      (node (ref "ATF22V10C") (pin "4") (pinfunction "NC2_4") (pintype "bidirectional"))
    )
    (net (code "84") (name "unconnected-(ATF22V10C-NC5-Pad23)") (class "Default")
      (node (ref "ATF22V10C") (pin "23") (pinfunction "NC5_23") (pintype "bidirectional"))
    )
    (net (code "85") (name "unconnected-(IC2B-O-Pad6)") (class "Default")
      (node (ref "IC2") (pin "6") (pinfunction "O_6") (pintype "output"))
    )
    (net (code "86") (name "unconnected-(IC2C-O-Pad8)") (class "Default")
      (node (ref "IC2") (pin "8") (pinfunction "O_8") (pintype "output"))
    )
    (net (code "87") (name "unconnected-(IC2D-O-Pad11)") (class "Default")
      (node (ref "IC2") (pin "11") (pinfunction "O_11") (pintype "output"))
    )
    (net (code "88") (name "unconnected-(JOYSTICK1-Pad1)") (class "Default")
      (node (ref "JOYSTICK1") (pin "1") (pinfunction "1_1") (pintype "passive"))
    )
    (net (code "89") (name "unconnected-(JOYSTICK1-Pad6)") (class "Default")
      (node (ref "JOYSTICK1") (pin "6") (pinfunction "6_6") (pintype "passive"))
    )
    (net (code "90") (name "unconnected-(JOYSTICK1-Pad8)") (class "Default")
      (node (ref "JOYSTICK1") (pin "8") (pinfunction "8_8") (pintype "passive"))
    )
    (net (code "91") (name "unconnected-(JOYSTICK2-Pad1)") (class "Default")
      (node (ref "JOYSTICK2") (pin "1") (pinfunction "1_1") (pintype "passive"))
    )
    (net (code "92") (name "unconnected-(JOYSTICK2-Pad6)") (class "Default")
      (node (ref "JOYSTICK2") (pin "6") (pinfunction "6_6") (pintype "passive"))
    )
    (net (code "93") (name "unconnected-(JOYSTICK2-Pad8)") (class "Default")
      (node (ref "JOYSTICK2") (pin "8") (pinfunction "8_8") (pintype "passive"))
    )
    (net (code "94") (name "unconnected-(R8-A-Pad1)") (class "Default")
      (node (ref "R8") (pin "1") (pinfunction "A_1") (pintype "passive"))
    )
    (net (code "95") (name "unconnected-(S1-S-Pad3)") (class "Default")
      (node (ref "S1") (pin "3") (pinfunction "S_3") (pintype "passive"))
    )
    (net (code "96") (name "unconnected-(U$1-A8-PadP$11)") (class "Default")
      (node (ref "U$1") (pin "P$11") (pinfunction "A8_P$11") (pintype "bidirectional"))
    )
    (net (code "97") (name "unconnected-(U$1-A9-PadP$17)") (class "Default")
      (node (ref "U$1") (pin "P$17") (pinfunction "A9_P$17") (pintype "bidirectional"))
    )
    (net (code "98") (name "unconnected-(U$1-A10-PadP$4)") (class "Default")
      (node (ref "U$1") (pin "P$4") (pinfunction "A10_P$4") (pintype "bidirectional"))
    )
    (net (code "99") (name "unconnected-(U$1-A11-PadP$9)") (class "Default")
      (node (ref "U$1") (pin "P$9") (pinfunction "A11_P$9") (pintype "bidirectional"))
    )
    (net (code "100") (name "unconnected-(U$1-A12-PadP$5)") (class "Default")
      (node (ref "U$1") (pin "P$5") (pinfunction "A12_P$5") (pintype "bidirectional"))
    )
    (net (code "101") (name "unconnected-(U$1-A13-PadP$6)") (class "Default")
      (node (ref "U$1") (pin "P$6") (pinfunction "A13_P$6") (pintype "bidirectional"))
    )
    (net (code "102") (name "unconnected-(U$1-A14-PadP$10)") (class "Default")
      (node (ref "U$1") (pin "P$10") (pinfunction "A14_P$10") (pintype "bidirectional"))
    )
    (net (code "103") (name "unconnected-(U$1-A15-PadP$7)") (class "Default")
      (node (ref "U$1") (pin "P$7") (pinfunction "A15_P$7") (pintype "bidirectional"))
    )
    (net (code "104") (name "unconnected-(U$1-CAS*-PadP$3)") (class "Default")
      (node (ref "U$1") (pin "P$3") (pinfunction "CAS*_P$3") (pintype "bidirectional"))
    )
    (net (code "105") (name "unconnected-(U$1-GND3-PadP$37)") (class "Default")
      (node (ref "U$1") (pin "P$37") (pinfunction "GND3_P$37") (pintype "bidirectional"))
    )
    (net (code "106") (name "unconnected-(U$1-INTAK*-PadP$14)") (class "Default")
      (node (ref "U$1") (pin "P$14") (pinfunction "INTAK*_P$14") (pintype "bidirectional"))
    )
    (net (code "107") (name "unconnected-(U$1-MUX-PadP$16)") (class "Default")
      (node (ref "U$1") (pin "P$16") (pinfunction "MUX_P$16") (pintype "bidirectional"))
    )
    (net (code "108") (name "unconnected-(U$1-NC-PadP$39)") (class "Default")
      (node (ref "U$1") (pin "P$39") (pinfunction "NC_P$39") (pintype "bidirectional"))
    )
    (net (code "109") (name "unconnected-(U$1-RAS*-PadP$1)") (class "Default")
      (node (ref "U$1") (pin "P$1") (pinfunction "RAS*_P$1") (pintype "bidirectional"))
    )
    (net (code "110") (name "unconnected-(U$1-RD*-PadP$15)") (class "Default")
      (node (ref "U$1") (pin "P$15") (pinfunction "RD*_P$15") (pintype "bidirectional"))
    )
    (net (code "111") (name "unconnected-(U$1-TEST*-PadP$23)") (class "Default")
      (node (ref "U$1") (pin "P$23") (pinfunction "TEST*_P$23") (pintype "bidirectional"))
    )
    (net (code "112") (name "unconnected-(U$1-WR*-PadP$13)") (class "Default")
      (node (ref "U$1") (pin "P$13") (pinfunction "WR*_P$13") (pintype "bidirectional"))
    )
    (net (code "113") (name "unconnected-(U2-NC-PadP37)") (class "Default")
      (node (ref "U2") (pin "P37") (pinfunction "NC_P37") (pintype "bidirectional"))
    )
    (net (code "114") (name "unconnected-(U4-NC-PadP9)") (class "Default")
      (node (ref "U4") (pin "P9") (pinfunction "NC_P9") (pintype "bidirectional"))
    )
    (net (code "115") (name "unconnected-(U11-NC-PadP9)") (class "Default")
      (node (ref "U11") (pin "P9") (pinfunction "NC_P9") (pintype "bidirectional"))
    )
  )
)
